# BLE.net
KiCad netlist of a schematic drawn in EAGLE
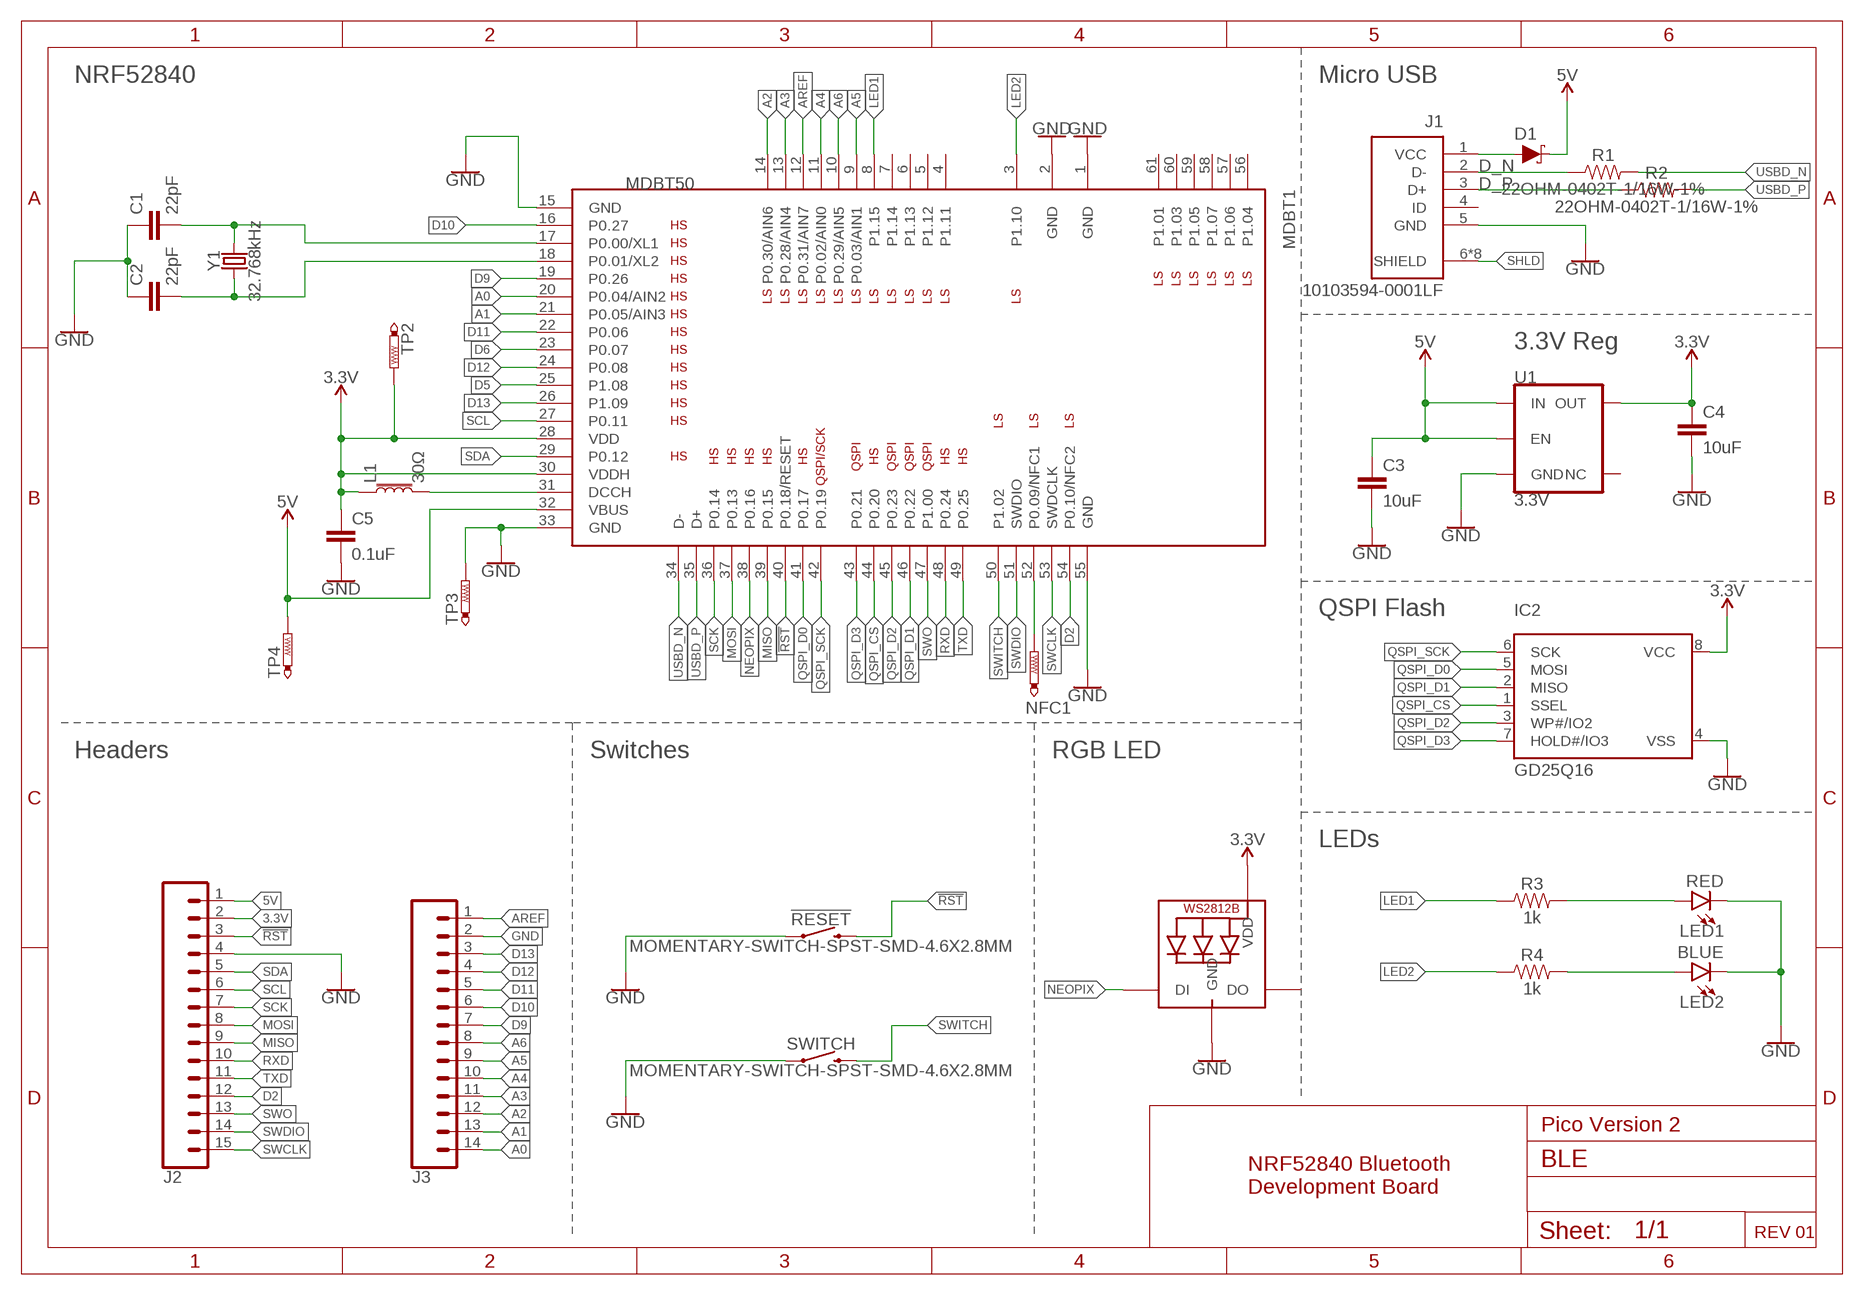
[diagram p0: schematic, sheet 1]

(export (version "E")
  (design (tool "Eeschema 10.0.6"))
  (components
    (comp (ref "!RESET!")
      (value "MOMENTARY-SWITCH-SPST-SMD-4.6X2.8MM")
      (footprint "eagle-import:TACTILE_SWITCH_SMD_4.6X2.8MM")
      (libsource (lib "eagle-import") (part "MOMENTARY-SWITCH-SPST-SMD-4.6X2.8MM"))
    )
    (comp (ref "C1")
      (value "22pF")
      (footprint "eagle-import:0402-TIGHT")
      (libsource (lib "eagle-import") (part "22PF-0402T-16V-10%"))
    )
    (comp (ref "C2")
      (value "22pF")
      (footprint "eagle-import:0402-TIGHT")
      (libsource (lib "eagle-import") (part "22PF-0402T-16V-10%"))
    )
    (comp (ref "C3")
      (value "10uF")
      (footprint "eagle-import:0603")
      (libsource (lib "eagle-import") (part "10UF-0603-6.3V-20%"))
    )
    (comp (ref "C4")
      (value "10uF")
      (footprint "eagle-import:0603")
      (libsource (lib "eagle-import") (part "10UF-0603-6.3V-20%"))
    )
    (comp (ref "C5")
      (value "0.1uF")
      (footprint "eagle-import:0402-TIGHT")
      (libsource (lib "eagle-import") (part "0.1UF-0402T-10V-10%-X7R"))
    )
    (comp (ref "D1")
      (value "0.5A/40V/420mV")
      (footprint "eagle-import:SOD-323")
      (libsource (lib "eagle-import") (part "DIODE-SCHOTTKY-PMEG4005EJ"))
    )
    (comp (ref "IC2")
      (value "GD25Q16")
      (footprint "eagle-import:USON8")
      (libsource (lib "eagle-import") (part "SPIFLASH_8PINUX"))
    )
    (comp (ref "J1")
      (value "10103594-0001LF")
      (footprint "eagle-import:AMPHENOL_10103594-0001LF")
      (fields (field (name "MF") "Amphenol ICC (FCI)"))
      (libsource (lib "eagle-import") (part "10103594-0001LF"))
    )
    (comp (ref "J2")
      (value "CONN_15")
      (footprint "eagle-import:1X15")
      (libsource (lib "eagle-import") (part "CONN_15"))
    )
    (comp (ref "J3")
      (value "CONN_14")
      (footprint "eagle-import:1X14")
      (libsource (lib "eagle-import") (part "CONN_14"))
    )
    (comp (ref "L1")
      (value "30Ω")
      (footprint "eagle-import:0402-TIGHT")
      (libsource (lib "eagle-import") (part "FERRITE_BEAD-0402-30OHM-100MHZ"))
    )
    (comp (ref "LED1")
      (value "RED")
      (footprint "eagle-import:LED-0603")
      (libsource (lib "eagle-import") (part "LED-RED0603"))
    )
    (comp (ref "LED2")
      (value "BLUE")
      (footprint "eagle-import:LED-0603")
      (libsource (lib "eagle-import") (part "LED-BLUE0603"))
    )
    (comp (ref "MDBT1")
      (value "MDBT50")
      (footprint "eagle-import:MDBT50")
      (libsource (lib "eagle-import") (part "MDBT50"))
    )
    (comp (ref "NFC1")
      (value "PTR1TP10R")
      (footprint "eagle-import:TP10R")
      (libsource (lib "eagle-import") (part "PTR1TP10R"))
    )
    (comp (ref "R1")
      (value "22OHM-0402T-1/16W-1%")
      (footprint "eagle-import:0402-TIGHT")
      (libsource (lib "eagle-import") (part "22OHM-0402T-1/16W-1%"))
    )
    (comp (ref "R2")
      (value "22OHM-0402T-1/16W-1%")
      (footprint "eagle-import:0402-TIGHT")
      (libsource (lib "eagle-import") (part "22OHM-0402T-1/16W-1%"))
    )
    (comp (ref "R3")
      (value "1k")
      (footprint "eagle-import:0402-TIGHT")
      (libsource (lib "eagle-import") (part "1KOHM-0402T-1/16W-1%"))
    )
    (comp (ref "R4")
      (value "1k")
      (footprint "eagle-import:0402-TIGHT")
      (libsource (lib "eagle-import") (part "1KOHM-0402T-1/16W-1%"))
    )
    (comp (ref "RGB_LED")
      (value "WS2812B_SK6805_1515")
      (footprint "eagle-import:SK6805_1515")
      (libsource (lib "eagle-import") (part "WS2812B_SK6805_1515"))
    )
    (comp (ref "SWITCH")
      (value "MOMENTARY-SWITCH-SPST-SMD-4.6X2.8MM")
      (footprint "eagle-import:TACTILE_SWITCH_SMD_4.6X2.8MM")
      (libsource (lib "eagle-import") (part "MOMENTARY-SWITCH-SPST-SMD-4.6X2.8MM"))
    )
    (comp (ref "TP2")
      (value "PTR1TP07R")
      (footprint "eagle-import:TP07R")
      (libsource (lib "eagle-import") (part "PTR1TP07R"))
    )
    (comp (ref "TP3")
      (value "PTR1TP07R")
      (footprint "eagle-import:TP07R")
      (libsource (lib "eagle-import") (part "PTR1TP07R"))
    )
    (comp (ref "TP4")
      (value "PTR1TP07R")
      (footprint "eagle-import:TP07R")
      (libsource (lib "eagle-import") (part "PTR1TP07R"))
    )
    (comp (ref "U1")
      (value "3.3V")
      (footprint "eagle-import:SOT23-5")
      (libsource (lib "eagle-import") (part "V_REG_AP2112K-3.3V"))
    )
    (comp (ref "Y1")
      (value "32.768kHz")
      (footprint "eagle-import:CRYSTAL-SMD-3.2X1.5MM")
      (libsource (lib "eagle-import") (part "CRYSTAL-32.768KHZSMD-3.2X1.5"))
    )
  )
  (nets
    (net (code "1") (name "/D_N") (class "Default")
      (node (ref "J1") (pin "2") (pinfunction "D-_2") (pintype "bidirectional"))
      (node (ref "R1") (pin "1") (pinfunction "1_1") (pintype "passive"))
    )
    (net (code "2") (name "/D_P") (class "Default")
      (node (ref "J1") (pin "3") (pinfunction "D+_3") (pintype "bidirectional"))
      (node (ref "R2") (pin "1") (pinfunction "1_1") (pintype "passive"))
    )
    (net (code "3") (name "/~{RST}") (class "Default")
      (node (ref "!RESET!") (pin "3") (pinfunction "2_3") (pintype "passive"))
      (node (ref "!RESET!") (pin "4") (pinfunction "2_4") (pintype "passive"))
      (node (ref "J2") (pin "3") (pinfunction "3_3") (pintype "passive"))
      (node (ref "MDBT1") (pin "40") (pinfunction "P0.18/RESET_40") (pintype "bidirectional"))
    )
    (net (code "4") (name "3.3V") (class "Default")
      (node (ref "C4") (pin "1") (pinfunction "1_1") (pintype "passive"))
      (node (ref "C5") (pin "1") (pinfunction "1_1") (pintype "passive"))
      (node (ref "IC2") (pin "8") (pinfunction "VCC_8") (pintype "bidirectional"))
      (node (ref "J2") (pin "2") (pinfunction "2_2") (pintype "passive"))
      (node (ref "L1") (pin "1") (pinfunction "1_1") (pintype "passive"))
      (node (ref "MDBT1") (pin "28") (pinfunction "VDD_28") (pintype "bidirectional"))
      (node (ref "MDBT1") (pin "30") (pinfunction "VDDH_30") (pintype "bidirectional"))
      (node (ref "RGB_LED") (pin "2") (pinfunction "VDD_2") (pintype "power_in"))
      (node (ref "TP2") (pin "TP") (pinfunction "TP_TP") (pintype "input"))
      (node (ref "U1") (pin "5") (pinfunction "OUT_5") (pintype "passive"))
    )
    (net (code "5") (name "5V") (class "Default")
      (node (ref "C3") (pin "1") (pinfunction "1_1") (pintype "passive"))
      (node (ref "D1") (pin "C") (pinfunction "C_C") (pintype "passive"))
      (node (ref "J2") (pin "1") (pinfunction "1_1") (pintype "passive"))
      (node (ref "MDBT1") (pin "32") (pinfunction "VBUS_32") (pintype "bidirectional"))
      (node (ref "TP4") (pin "TP") (pinfunction "TP_TP") (pintype "input"))
      (node (ref "U1") (pin "1") (pinfunction "IN_1") (pintype "input"))
      (node (ref "U1") (pin "3") (pinfunction "EN_3") (pintype "input"))
    )
    (net (code "6") (name "A0") (class "Default")
      (node (ref "J3") (pin "14") (pinfunction "14_14") (pintype "passive"))
      (node (ref "MDBT1") (pin "20") (pinfunction "P0.04/AIN2_20") (pintype "bidirectional"))
    )
    (net (code "7") (name "A1") (class "Default")
      (node (ref "J3") (pin "13") (pinfunction "13_13") (pintype "passive"))
      (node (ref "MDBT1") (pin "21") (pinfunction "P0.05/AIN3_21") (pintype "bidirectional"))
    )
    (net (code "8") (name "A2") (class "Default")
      (node (ref "J3") (pin "12") (pinfunction "12_12") (pintype "passive"))
      (node (ref "MDBT1") (pin "14") (pinfunction "P0.30/AIN6_14") (pintype "bidirectional"))
    )
    (net (code "9") (name "A3") (class "Default")
      (node (ref "J3") (pin "11") (pinfunction "11_11") (pintype "passive"))
      (node (ref "MDBT1") (pin "13") (pinfunction "P0.28/AIN4_13") (pintype "bidirectional"))
    )
    (net (code "10") (name "A4") (class "Default")
      (node (ref "J3") (pin "10") (pinfunction "10_10") (pintype "passive"))
      (node (ref "MDBT1") (pin "11") (pinfunction "P0.02/AIN0_11") (pintype "bidirectional"))
    )
    (net (code "11") (name "A5") (class "Default")
      (node (ref "J3") (pin "9") (pinfunction "9_9") (pintype "passive"))
      (node (ref "MDBT1") (pin "9") (pinfunction "P0.03/AIN1_9") (pintype "bidirectional"))
    )
    (net (code "12") (name "A6") (class "Default")
      (node (ref "J3") (pin "8") (pinfunction "8_8") (pintype "passive"))
      (node (ref "MDBT1") (pin "10") (pinfunction "P0.29/AIN5_10") (pintype "bidirectional"))
    )
    (net (code "13") (name "AREF") (class "Default")
      (node (ref "J3") (pin "1") (pinfunction "1_1") (pintype "passive"))
      (node (ref "MDBT1") (pin "12") (pinfunction "P0.31/AIN7_12") (pintype "bidirectional"))
    )
    (net (code "14") (name "D2") (class "Default")
      (node (ref "J2") (pin "12") (pinfunction "12_12") (pintype "passive"))
      (node (ref "MDBT1") (pin "54") (pinfunction "P0.10/NFC2_54") (pintype "bidirectional"))
    )
    (net (code "15") (name "D5") (class "Default")
      (node (ref "MDBT1") (pin "25") (pinfunction "P1.08_25") (pintype "bidirectional"))
    )
    (net (code "16") (name "D6") (class "Default")
      (node (ref "MDBT1") (pin "23") (pinfunction "P0.07_23") (pintype "bidirectional"))
    )
    (net (code "17") (name "D9") (class "Default")
      (node (ref "J3") (pin "7") (pinfunction "7_7") (pintype "passive"))
      (node (ref "MDBT1") (pin "19") (pinfunction "P0.26_19") (pintype "bidirectional"))
    )
    (net (code "18") (name "D10") (class "Default")
      (node (ref "J3") (pin "6") (pinfunction "6_6") (pintype "passive"))
      (node (ref "MDBT1") (pin "16") (pinfunction "P0.27_16") (pintype "bidirectional"))
    )
    (net (code "19") (name "D11") (class "Default")
      (node (ref "J3") (pin "5") (pinfunction "5_5") (pintype "passive"))
      (node (ref "MDBT1") (pin "22") (pinfunction "P0.06_22") (pintype "bidirectional"))
    )
    (net (code "20") (name "D12") (class "Default")
      (node (ref "J3") (pin "4") (pinfunction "4_4") (pintype "passive"))
      (node (ref "MDBT1") (pin "24") (pinfunction "P0.08_24") (pintype "bidirectional"))
    )
    (net (code "21") (name "D13") (class "Default")
      (node (ref "J3") (pin "3") (pinfunction "3_3") (pintype "passive"))
      (node (ref "MDBT1") (pin "26") (pinfunction "P1.09_26") (pintype "bidirectional"))
    )
    (net (code "22") (name "GND") (class "Default")
      (node (ref "!RESET!") (pin "1") (pinfunction "1_1") (pintype "passive"))
      (node (ref "!RESET!") (pin "2") (pinfunction "1_2") (pintype "passive"))
      (node (ref "C1") (pin "1") (pinfunction "1_1") (pintype "passive"))
      (node (ref "C2") (pin "1") (pinfunction "1_1") (pintype "passive"))
      (node (ref "C3") (pin "2") (pinfunction "2_2") (pintype "passive"))
      (node (ref "C4") (pin "2") (pinfunction "2_2") (pintype "passive"))
      (node (ref "C5") (pin "2") (pinfunction "2_2") (pintype "passive"))
      (node (ref "IC2") (pin "4") (pinfunction "VSS_4") (pintype "bidirectional"))
      (node (ref "J1") (pin "5") (pinfunction "GND_5") (pintype "power_in"))
      (node (ref "J2") (pin "4") (pinfunction "4_4") (pintype "passive"))
      (node (ref "J3") (pin "2") (pinfunction "2_2") (pintype "passive"))
      (node (ref "LED1") (pin "C") (pinfunction "C_C") (pintype "passive"))
      (node (ref "LED2") (pin "C") (pinfunction "C_C") (pintype "passive"))
      (node (ref "MDBT1") (pin "1") (pinfunction "GND_1") (pintype "bidirectional"))
      (node (ref "MDBT1") (pin "15") (pinfunction "GND_15") (pintype "bidirectional"))
      (node (ref "MDBT1") (pin "2") (pinfunction "GND_2") (pintype "bidirectional"))
      (node (ref "MDBT1") (pin "33") (pinfunction "GND_33") (pintype "bidirectional"))
      (node (ref "MDBT1") (pin "55") (pinfunction "GND_55") (pintype "bidirectional"))
      (node (ref "RGB_LED") (pin "4") (pinfunction "GND_4") (pintype "power_in"))
      (node (ref "SWITCH") (pin "1") (pinfunction "1_1") (pintype "passive"))
      (node (ref "SWITCH") (pin "2") (pinfunction "1_2") (pintype "passive"))
      (node (ref "TP3") (pin "TP") (pinfunction "TP_TP") (pintype "input"))
      (node (ref "U1") (pin "2") (pinfunction "GND_2") (pintype "input"))
    )
    (net (code "23") (name "LED1") (class "Default")
      (node (ref "MDBT1") (pin "8") (pinfunction "P1.15_8") (pintype "bidirectional"))
      (node (ref "R3") (pin "1") (pinfunction "1_1") (pintype "passive"))
    )
    (net (code "24") (name "LED2") (class "Default")
      (node (ref "MDBT1") (pin "3") (pinfunction "P1.10_3") (pintype "bidirectional"))
      (node (ref "R4") (pin "1") (pinfunction "1_1") (pintype "passive"))
    )
    (net (code "25") (name "MISO") (class "Default")
      (node (ref "J2") (pin "9") (pinfunction "9_9") (pintype "passive"))
      (node (ref "MDBT1") (pin "39") (pinfunction "P0.15_39") (pintype "bidirectional"))
    )
    (net (code "26") (name "MOSI") (class "Default")
      (node (ref "J2") (pin "8") (pinfunction "8_8") (pintype "passive"))
      (node (ref "MDBT1") (pin "37") (pinfunction "P0.13_37") (pintype "bidirectional"))
    )
    (net (code "27") (name "NEOPIX") (class "Default")
      (node (ref "MDBT1") (pin "38") (pinfunction "P0.16_38") (pintype "bidirectional"))
      (node (ref "RGB_LED") (pin "1") (pinfunction "DI_1") (pintype "input"))
    )
    (net (code "28") (name "Net-(J1-VCC)") (class "Default")
      (node (ref "D1") (pin "A") (pinfunction "A_A") (pintype "passive"))
      (node (ref "J1") (pin "1") (pinfunction "VCC_1") (pintype "power_in"))
    )
    (net (code "29") (name "Net-(LED1-PadA)") (class "Default")
      (node (ref "LED1") (pin "A") (pinfunction "A_A") (pintype "passive"))
      (node (ref "R3") (pin "2") (pinfunction "2_2") (pintype "passive"))
    )
    (net (code "30") (name "Net-(LED2-PadA)") (class "Default")
      (node (ref "LED2") (pin "A") (pinfunction "A_A") (pintype "passive"))
      (node (ref "R4") (pin "2") (pinfunction "2_2") (pintype "passive"))
    )
    (net (code "31") (name "Net-(MDBT1-DCCH)") (class "Default")
      (node (ref "L1") (pin "2") (pinfunction "2_2") (pintype "passive"))
      (node (ref "MDBT1") (pin "31") (pinfunction "DCCH_31") (pintype "bidirectional"))
    )
    (net (code "32") (name "Net-(MDBT1-P0.00{slash}XL1)") (class "Default")
      (node (ref "C1") (pin "2") (pinfunction "2_2") (pintype "passive"))
      (node (ref "MDBT1") (pin "17") (pinfunction "P0.00/XL1_17") (pintype "bidirectional"))
      (node (ref "Y1") (pin "P$2") (pinfunction "2_P$2") (pintype "passive"))
    )
    (net (code "33") (name "Net-(MDBT1-P0.01{slash}XL2)") (class "Default")
      (node (ref "C2") (pin "2") (pinfunction "2_2") (pintype "passive"))
      (node (ref "MDBT1") (pin "18") (pinfunction "P0.01/XL2_18") (pintype "bidirectional"))
      (node (ref "Y1") (pin "P$1") (pinfunction "1_P$1") (pintype "passive"))
    )
    (net (code "34") (name "Net-(MDBT1-P0.09{slash}NFC1)") (class "Default")
      (node (ref "MDBT1") (pin "52") (pinfunction "P0.09/NFC1_52") (pintype "bidirectional"))
      (node (ref "NFC1") (pin "TP") (pinfunction "TP_TP") (pintype "input"))
    )
    (net (code "35") (name "QSPI_CS") (class "Default")
      (node (ref "IC2") (pin "1") (pinfunction "SSEL_1") (pintype "bidirectional"))
      (node (ref "MDBT1") (pin "44") (pinfunction "P0.20_44") (pintype "bidirectional"))
    )
    (net (code "36") (name "QSPI_D0") (class "Default")
      (node (ref "IC2") (pin "5") (pinfunction "MOSI_5") (pintype "bidirectional"))
      (node (ref "MDBT1") (pin "41") (pinfunction "P0.17_41") (pintype "bidirectional"))
    )
    (net (code "37") (name "QSPI_D1") (class "Default")
      (node (ref "IC2") (pin "2") (pinfunction "MISO_2") (pintype "bidirectional"))
      (node (ref "MDBT1") (pin "46") (pinfunction "P0.22_46") (pintype "bidirectional"))
    )
    (net (code "38") (name "QSPI_D2") (class "Default")
      (node (ref "IC2") (pin "3") (pinfunction "WP#/IO2_3") (pintype "bidirectional"))
      (node (ref "MDBT1") (pin "45") (pinfunction "P0.23_45") (pintype "bidirectional"))
    )
    (net (code "39") (name "QSPI_D3") (class "Default")
      (node (ref "IC2") (pin "7") (pinfunction "HOLD#/IO3_7") (pintype "bidirectional"))
      (node (ref "MDBT1") (pin "43") (pinfunction "P0.21_43") (pintype "bidirectional"))
    )
    (net (code "40") (name "QSPI_SCK") (class "Default")
      (node (ref "IC2") (pin "6") (pinfunction "SCK_6") (pintype "bidirectional"))
      (node (ref "MDBT1") (pin "42") (pinfunction "P0.19_42") (pintype "bidirectional"))
    )
    (net (code "41") (name "RXD") (class "Default")
      (node (ref "J2") (pin "10") (pinfunction "10_10") (pintype "passive"))
      (node (ref "MDBT1") (pin "48") (pinfunction "P0.24_48") (pintype "bidirectional"))
    )
    (net (code "42") (name "SCK") (class "Default")
      (node (ref "J2") (pin "7") (pinfunction "7_7") (pintype "passive"))
      (node (ref "MDBT1") (pin "36") (pinfunction "P0.14_36") (pintype "bidirectional"))
    )
    (net (code "43") (name "SCL") (class "Default")
      (node (ref "J2") (pin "6") (pinfunction "6_6") (pintype "passive"))
      (node (ref "MDBT1") (pin "27") (pinfunction "P0.11_27") (pintype "bidirectional"))
    )
    (net (code "44") (name "SDA") (class "Default")
      (node (ref "J2") (pin "5") (pinfunction "5_5") (pintype "passive"))
      (node (ref "MDBT1") (pin "29") (pinfunction "P0.12_29") (pintype "bidirectional"))
    )
    (net (code "45") (name "SHLD") (class "Default")
      (node (ref "J1") (pin "10") (pinfunction "SHIELD_10") (pintype "passive"))
      (node (ref "J1") (pin "11") (pinfunction "SHIELD_11") (pintype "passive"))
      (node (ref "J1") (pin "6") (pinfunction "SHIELD_6") (pintype "passive"))
      (node (ref "J1") (pin "7") (pinfunction "SHIELD_7") (pintype "passive"))
      (node (ref "J1") (pin "8") (pinfunction "SHIELD_8") (pintype "passive"))
      (node (ref "J1") (pin "9") (pinfunction "SHIELD_9") (pintype "passive"))
      (node (ref "J1") (pin "S1") (pinfunction "SHIELD_S1") (pintype "passive"))
      (node (ref "J1") (pin "S2") (pinfunction "SHIELD_S2") (pintype "passive"))
    )
    (net (code "46") (name "SWCLK") (class "Default")
      (node (ref "J2") (pin "15") (pinfunction "15_15") (pintype "passive"))
      (node (ref "MDBT1") (pin "53") (pinfunction "SWDCLK_53") (pintype "bidirectional"))
    )
    (net (code "47") (name "SWDIO") (class "Default")
      (node (ref "J2") (pin "14") (pinfunction "14_14") (pintype "passive"))
      (node (ref "MDBT1") (pin "51") (pinfunction "SWDIO_51") (pintype "bidirectional"))
    )
    (net (code "48") (name "SWITCH") (class "Default")
      (node (ref "MDBT1") (pin "50") (pinfunction "P1.02_50") (pintype "bidirectional"))
      (node (ref "SWITCH") (pin "3") (pinfunction "2_3") (pintype "passive"))
      (node (ref "SWITCH") (pin "4") (pinfunction "2_4") (pintype "passive"))
    )
    (net (code "49") (name "SWO") (class "Default")
      (node (ref "J2") (pin "13") (pinfunction "13_13") (pintype "passive"))
      (node (ref "MDBT1") (pin "47") (pinfunction "P1.00_47") (pintype "bidirectional"))
    )
    (net (code "50") (name "TXD") (class "Default")
      (node (ref "J2") (pin "11") (pinfunction "11_11") (pintype "passive"))
      (node (ref "MDBT1") (pin "49") (pinfunction "P0.25_49") (pintype "bidirectional"))
    )
    (net (code "51") (name "USBD_N") (class "Default")
      (node (ref "MDBT1") (pin "34") (pinfunction "D-_34") (pintype "bidirectional"))
      (node (ref "R1") (pin "2") (pinfunction "2_2") (pintype "passive"))
    )
    (net (code "52") (name "USBD_P") (class "Default")
      (node (ref "MDBT1") (pin "35") (pinfunction "D+_35") (pintype "bidirectional"))
      (node (ref "R2") (pin "2") (pinfunction "2_2") (pintype "passive"))
    )
    (net (code "53") (name "unconnected-(J1-ID-Pad4)") (class "Default")
      (node (ref "J1") (pin "4") (pinfunction "ID_4") (pintype "bidirectional"))
    )
    (net (code "54") (name "unconnected-(MDBT1-P1.01-Pad61)") (class "Default")
      (node (ref "MDBT1") (pin "61") (pinfunction "P1.01_61") (pintype "bidirectional"))
    )
    (net (code "55") (name "unconnected-(MDBT1-P1.03-Pad60)") (class "Default")
      (node (ref "MDBT1") (pin "60") (pinfunction "P1.03_60") (pintype "bidirectional"))
    )
    (net (code "56") (name "unconnected-(MDBT1-P1.04-Pad56)") (class "Default")
      (node (ref "MDBT1") (pin "56") (pinfunction "P1.04_56") (pintype "bidirectional"))
    )
    (net (code "57") (name "unconnected-(MDBT1-P1.05-Pad59)") (class "Default")
      (node (ref "MDBT1") (pin "59") (pinfunction "P1.05_59") (pintype "bidirectional"))
    )
    (net (code "58") (name "unconnected-(MDBT1-P1.06-Pad57)") (class "Default")
      (node (ref "MDBT1") (pin "57") (pinfunction "P1.06_57") (pintype "bidirectional"))
    )
    (net (code "59") (name "unconnected-(MDBT1-P1.07-Pad58)") (class "Default")
      (node (ref "MDBT1") (pin "58") (pinfunction "P1.07_58") (pintype "bidirectional"))
    )
    (net (code "60") (name "unconnected-(MDBT1-P1.11-Pad4)") (class "Default")
      (node (ref "MDBT1") (pin "4") (pinfunction "P1.11_4") (pintype "bidirectional"))
    )
    (net (code "61") (name "unconnected-(MDBT1-P1.12-Pad5)") (class "Default")
      (node (ref "MDBT1") (pin "5") (pinfunction "P1.12_5") (pintype "bidirectional"))
    )
    (net (code "62") (name "unconnected-(MDBT1-P1.13-Pad6)") (class "Default")
      (node (ref "MDBT1") (pin "6") (pinfunction "P1.13_6") (pintype "bidirectional"))
    )
    (net (code "63") (name "unconnected-(MDBT1-P1.14-Pad7)") (class "Default")
      (node (ref "MDBT1") (pin "7") (pinfunction "P1.14_7") (pintype "bidirectional"))
    )
    (net (code "64") (name "unconnected-(RGB_LED-DO-Pad3)") (class "Default")
      (node (ref "RGB_LED") (pin "3") (pinfunction "DO_3") (pintype "output"))
    )
    (net (code "65") (name "unconnected-(U1-NC-Pad4)") (class "Default")
      (node (ref "U1") (pin "4") (pinfunction "NC_4") (pintype "no_connect"))
    )
  )
)
